# BI5.net
KiCad netlist of a schematic drawn in Altium Designer
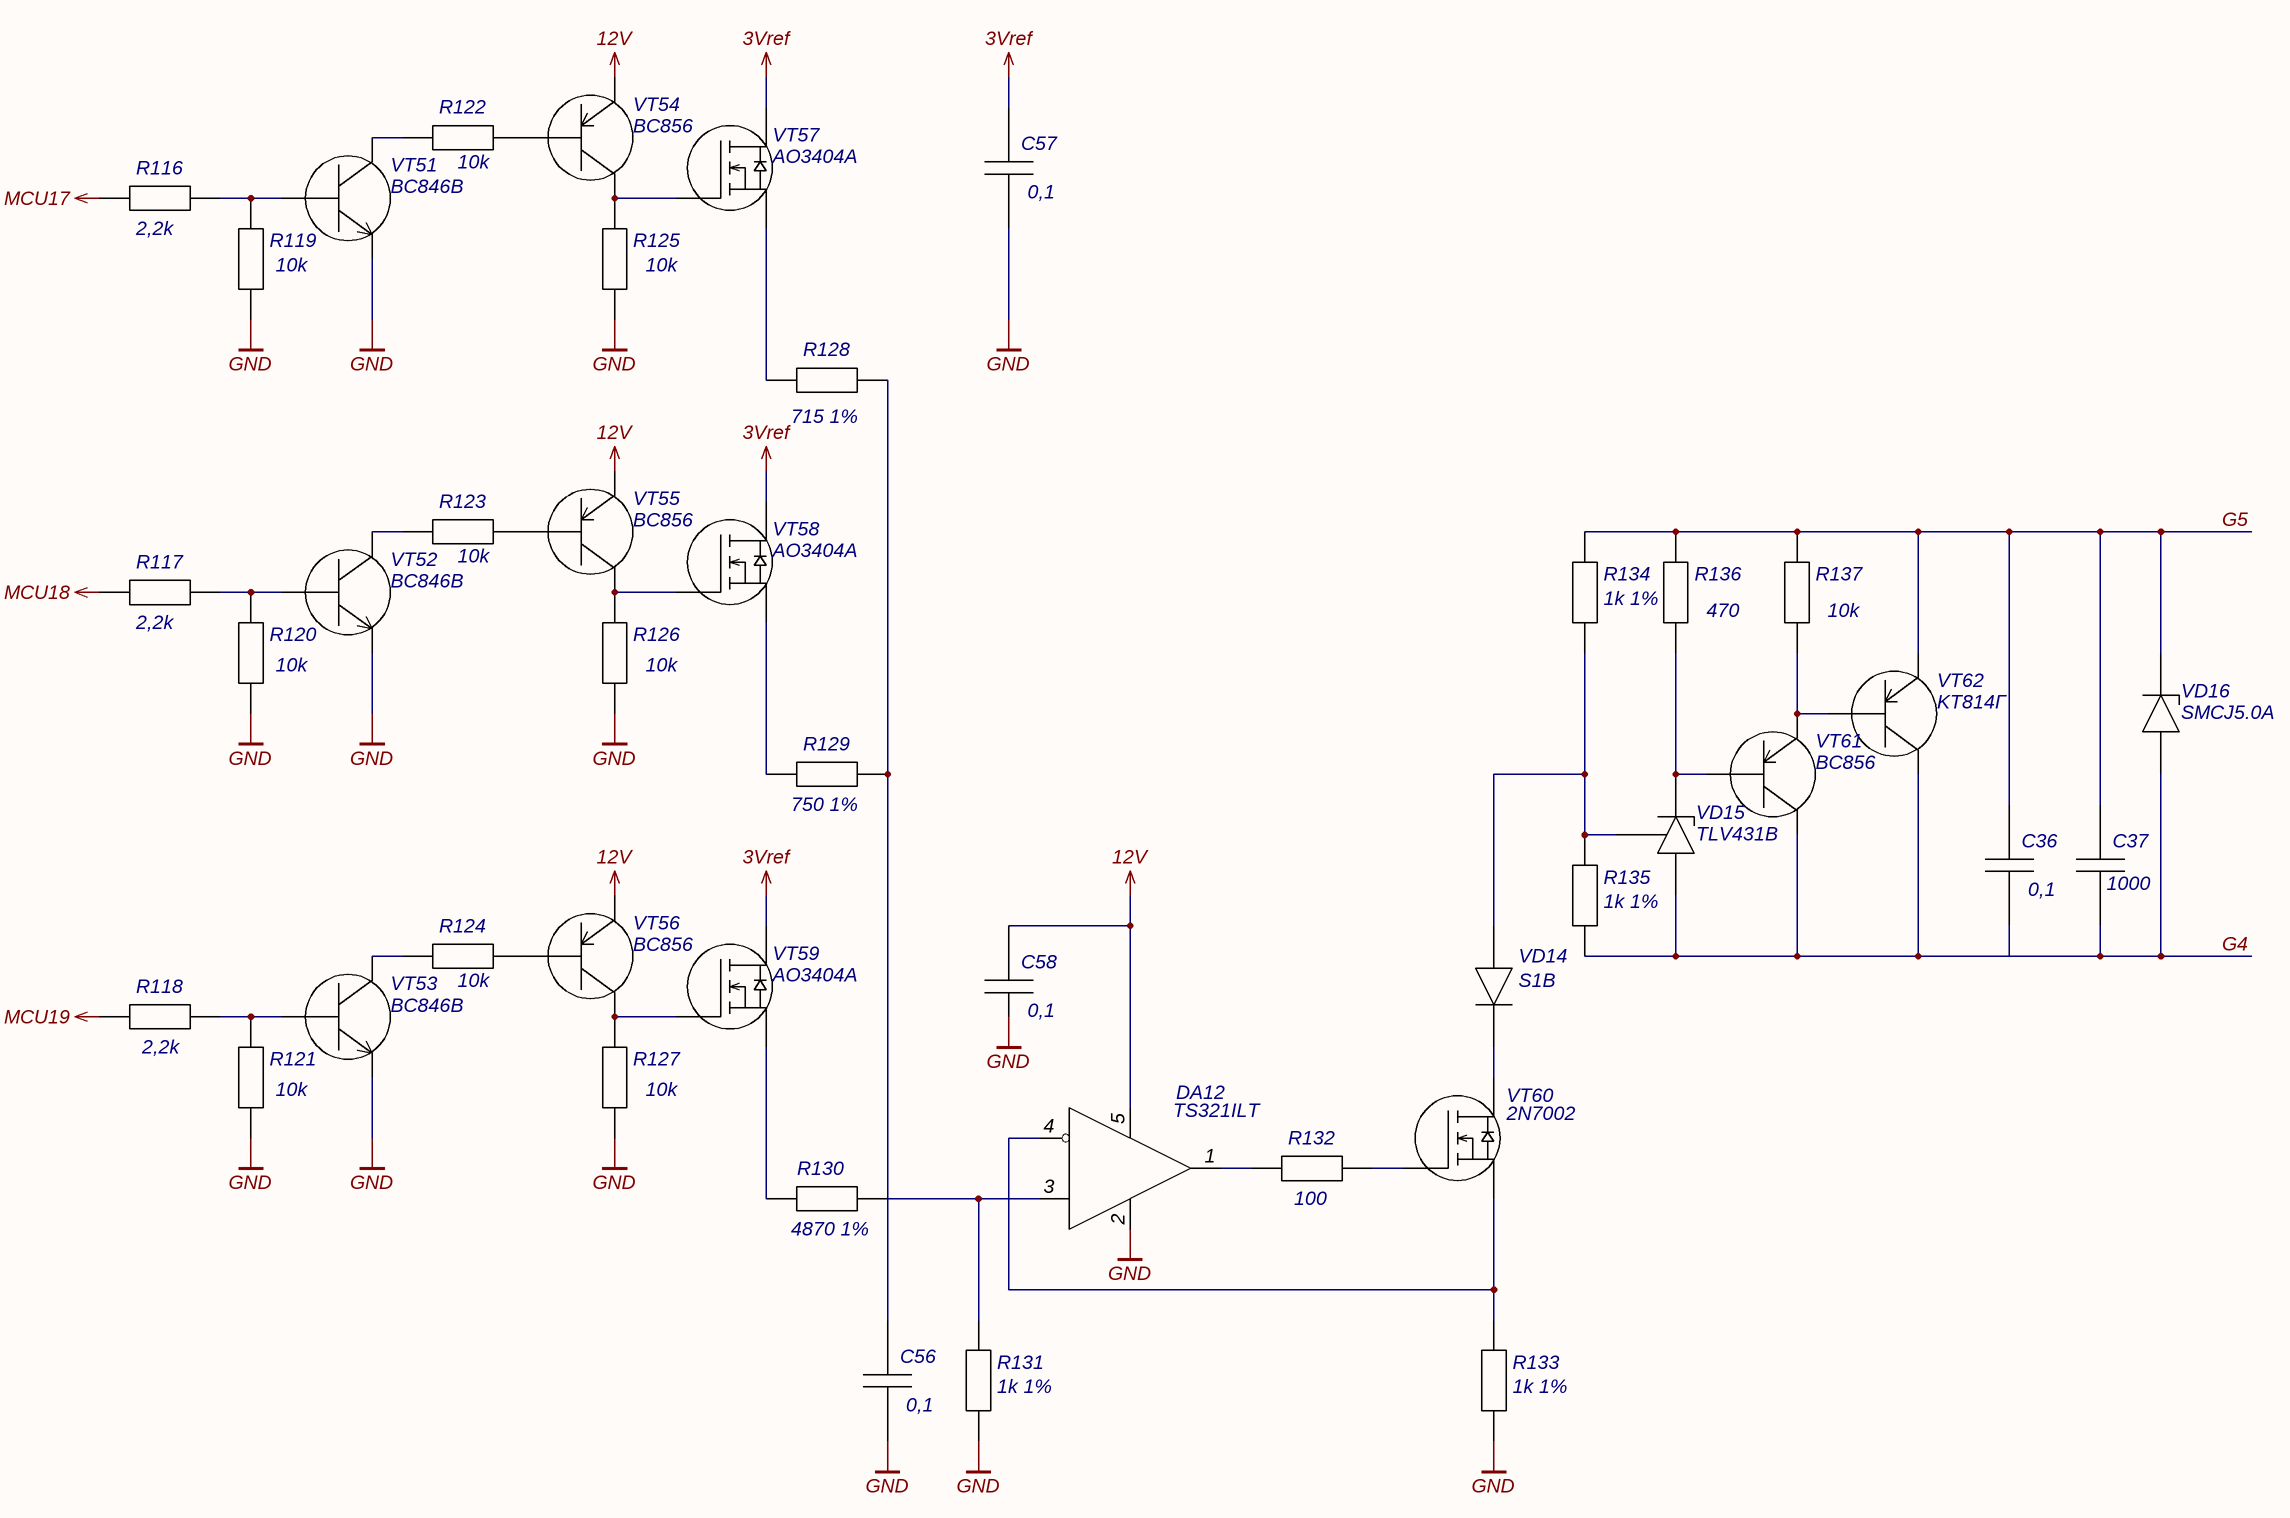
[diagram p0: BI5.SchDoc]

(export (version "E")
  (design (tool "Eeschema 10.0.6"))
  (components
    (comp (ref "C36")
      (value "0,1")
      (footprint "C0603")
      (description "Чип-конденсатор")
      (libsource (lib "Passive") (part "Chip Capasitor"))
    )
    (comp (ref "C37")
      (value "1000")
      (footprint "C0603")
      (description "Чип-конденсатор")
      (libsource (lib "Passive") (part "Chip Capasitor"))
    )
    (comp (ref "C56")
      (value "0,1")
      (footprint "C0603")
      (description "Чип-конденсатор")
      (libsource (lib "Passive") (part "Chip Capasitor"))
    )
    (comp (ref "C57")
      (value "0,1")
      (footprint "C0603")
      (description "Чип-конденсатор")
      (libsource (lib "Passive") (part "Chip Capasitor"))
    )
    (comp (ref "C58")
      (value "0,1")
      (footprint "C0603")
      (description "Чип-конденсатор")
      (libsource (lib "Passive") (part "Chip Capasitor"))
    )
    (comp (ref "DA12")
      (value "TS321ILT")
      (footprint "SOT-23-5")
      (description "1х Операционный усилитель")
      (libsource (lib "Schlib") (part "TS321ILT"))
    )
    (comp (ref "R116")
      (value "2,2k")
      (footprint "R0603")
      (description "Чип-резистор")
      (libsource (lib "Passive") (part "Chip Resistor"))
    )
    (comp (ref "R117")
      (value "2,2k")
      (footprint "R0603")
      (description "Чип-резистор")
      (libsource (lib "Passive") (part "Chip Resistor"))
    )
    (comp (ref "R118")
      (value "2,2k")
      (footprint "R0603")
      (description "Чип-резистор")
      (libsource (lib "Passive") (part "Chip Resistor"))
    )
    (comp (ref "R119")
      (value "10k")
      (footprint "R0603")
      (description "Чип-резистор")
      (libsource (lib "") (part "Chip Resistor_1"))
    )
    (comp (ref "R120")
      (value "10k")
      (footprint "R0603")
      (description "Чип-резистор")
      (libsource (lib "") (part "Chip Resistor_1"))
    )
    (comp (ref "R121")
      (value "10k")
      (footprint "R0603")
      (description "Чип-резистор")
      (libsource (lib "") (part "Chip Resistor_1"))
    )
    (comp (ref "R122")
      (value "10k")
      (footprint "R0603")
      (description "Чип-резистор")
      (libsource (lib "Passive") (part "Chip Resistor"))
    )
    (comp (ref "R123")
      (value "10k")
      (footprint "R0603")
      (description "Чип-резистор")
      (libsource (lib "Passive") (part "Chip Resistor"))
    )
    (comp (ref "R124")
      (value "10k")
      (footprint "R0603")
      (description "Чип-резистор")
      (libsource (lib "Passive") (part "Chip Resistor"))
    )
    (comp (ref "R125")
      (value "10k")
      (footprint "R0603")
      (description "Чип-резистор")
      (libsource (lib "") (part "Chip Resistor_1"))
    )
    (comp (ref "R126")
      (value "10k")
      (footprint "R0603")
      (description "Чип-резистор")
      (libsource (lib "") (part "Chip Resistor_1"))
    )
    (comp (ref "R127")
      (value "10k")
      (footprint "R0603")
      (description "Чип-резистор")
      (libsource (lib "") (part "Chip Resistor_1"))
    )
    (comp (ref "R128")
      (value "715 1%")
      (footprint "R0603")
      (description "Чип-резистор")
      (fields (field (name "PARTNUMBER") "RC0603FR-07715RL"))
      (libsource (lib "Passive") (part "Chip Resistor"))
    )
    (comp (ref "R129")
      (value "750 1%")
      (footprint "R0603")
      (description "Чип-резистор")
      (fields (field (name "PARTNUMBER") "RC0603FR-07750RL"))
      (libsource (lib "Passive") (part "Chip Resistor"))
    )
    (comp (ref "R130")
      (value "4870 1%")
      (footprint "R0603")
      (description "Чип-резистор")
      (fields (field (name "PARTNUMBER") "RC0603FR-074K87L"))
      (libsource (lib "Passive") (part "Chip Resistor"))
    )
    (comp (ref "R131")
      (value "1k 1%")
      (footprint "R0603")
      (description "Чип-резистор")
      (fields (field (name "PARTNUMBER") "CRCW06031K00FKEAC"))
      (libsource (lib "") (part "Chip Resistor_1"))
    )
    (comp (ref "R132")
      (value "100")
      (footprint "R0603")
      (description "Чип-резистор")
      (libsource (lib "Passive") (part "Chip Resistor"))
    )
    (comp (ref "R133")
      (value "1k 1%")
      (footprint "R0603")
      (description "Чип-резистор")
      (fields (field (name "PARTNUMBER") "CRCW06031K00FKEAC"))
      (libsource (lib "") (part "Chip Resistor_1"))
    )
    (comp (ref "R134")
      (value "1k 1%")
      (footprint "R0603")
      (description "Чип-резистор")
      (fields (field (name "PARTNUMBER") "CRCW06031K00FKEAC"))
      (libsource (lib "") (part "Chip Resistor_1"))
    )
    (comp (ref "R135")
      (value "1k 1%")
      (footprint "R0603")
      (description "Чип-резистор")
      (fields (field (name "PARTNUMBER") "CRCW06031K00FKEAC"))
      (libsource (lib "") (part "Chip Resistor_1"))
    )
    (comp (ref "R136")
      (value "470")
      (footprint "R0603")
      (description "Чип-резистор")
      (libsource (lib "") (part "Chip Resistor_1"))
    )
    (comp (ref "R137")
      (value "10k")
      (footprint "R0603")
      (description "Чип-резистор")
      (libsource (lib "") (part "Chip Resistor_1"))
    )
    (comp (ref "VD14")
      (value "S1B")
      (footprint "DO-214AC")
      (description "Диод выпрямительный, 100В")
      (fields (field (name "MANUFACTURER") "Diotec Semiconductor"))
      (libsource (lib "Schlib") (part "S1B"))
    )
    (comp (ref "VD15")
      (value "TLV431B")
      (footprint "SOT-23")
      (description "Стабилитрон регулируемый, 6В")
      (fields (field (name "MANUFACTURER") "Texas Instruments"))
      (libsource (lib "Schlib") (part "TLV431B"))
    )
    (comp (ref "VD16")
      (value "SMCJ5.0A")
      (footprint "DO-214AB")
      (description "Защитный диод, 5В")
      (fields (field (name "MANUFACTURER") "UTD Semiconductor Co.,Ltd"))
      (libsource (lib "Schlib") (part "SMCJ5.0A"))
    )
    (comp (ref "VT51")
      (value "BC846B")
      (footprint "SOT-23")
      (description "Транзистор биполярный NPN, 65В")
      (fields (field (name "MANUFACTURER") "Nexperia B.V."))
      (libsource (lib "Schlib") (part "BC846B"))
    )
    (comp (ref "VT52")
      (value "BC846B")
      (footprint "SOT-23")
      (description "Транзистор биполярный NPN, 65В")
      (fields (field (name "MANUFACTURER") "Nexperia B.V."))
      (libsource (lib "Schlib") (part "BC846B"))
    )
    (comp (ref "VT53")
      (value "BC846B")
      (footprint "SOT-23")
      (description "Транзистор биполярный NPN, 65В")
      (fields (field (name "MANUFACTURER") "Nexperia B.V."))
      (libsource (lib "Schlib") (part "BC846B"))
    )
    (comp (ref "VT54")
      (value "BC856")
      (footprint "SOT-23")
      (description "Транзистор биполярный PNP, 65В")
      (fields (field (name "MANUFACTURER") "Nexperia"))
      (libsource (lib "Schlib") (part "BC856"))
    )
    (comp (ref "VT55")
      (value "BC856")
      (footprint "SOT-23")
      (description "Транзистор биполярный PNP, 65В")
      (fields (field (name "MANUFACTURER") "Nexperia"))
      (libsource (lib "Schlib") (part "BC856"))
    )
    (comp (ref "VT56")
      (value "BC856")
      (footprint "SOT-23")
      (description "Транзистор биполярный PNP, 65В")
      (fields (field (name "MANUFACTURER") "Nexperia"))
      (libsource (lib "Schlib") (part "BC856"))
    )
    (comp (ref "VT57")
      (value "AO3404A")
      (footprint "SOT-23")
      (description "Транзистор MOSFET N-канал, 30В")
      (fields (field (name "MANUFACTURER") "UTD Semiconductor Co.,Ltd"))
      (libsource (lib "Schlib") (part "AO3404A"))
    )
    (comp (ref "VT58")
      (value "AO3404A")
      (footprint "SOT-23")
      (description "Транзистор MOSFET N-канал, 30В")
      (fields (field (name "MANUFACTURER") "UTD Semiconductor Co.,Ltd"))
      (libsource (lib "Schlib") (part "AO3404A"))
    )
    (comp (ref "VT59")
      (value "AO3404A")
      (footprint "SOT-23")
      (description "Транзистор MOSFET N-канал, 30В")
      (fields (field (name "MANUFACTURER") "UTD Semiconductor Co.,Ltd"))
      (libsource (lib "Schlib") (part "AO3404A"))
    )
    (comp (ref "VT60")
      (value "2N7002")
      (footprint "SOT-23")
      (description "Транзистор MOSFET N-канал, 60В")
      (fields (field (name "MANUFACTURER") "UTD Semiconductor Co."))
      (libsource (lib "Schlib") (part "2N7002"))
    )
    (comp (ref "VT61")
      (value "BC856")
      (footprint "SOT-23")
      (description "Транзистор биполярный PNP, 65В")
      (fields (field (name "MANUFACTURER") "Nexperia"))
      (libsource (lib "Schlib") (part "BC856"))
    )
    (comp (ref "VT62")
      (value "KT814Г")
      (footprint "TO-126")
      (description "Транзистор биполярный PNP, 100В")
      (fields (field (name "MANUFACTURER") "АО «ГРУППА КРЕМНИЙ ЭЛ»"))
      (libsource (lib "Schlib") (part "KT814Г"))
    )
  )
  (nets
    (net (code "1") (name "/G4") (class "Default")
      (node (ref "C36") (pin "1") (pinfunction "1_1") (pintype "passive"))
      (node (ref "C37") (pin "1") (pinfunction "1_1") (pintype "passive"))
      (node (ref "R135") (pin "1") (pinfunction "1_1") (pintype "passive"))
      (node (ref "VD15") (pin "1") (pinfunction "1_1") (pintype "passive"))
      (node (ref "VD16") (pin "1") (pinfunction "1_1") (pintype "passive"))
      (node (ref "VT61") (pin "2") (pinfunction "2_2") (pintype "passive"))
      (node (ref "VT62") (pin "2") (pinfunction "2_2") (pintype "passive"))
    )
    (net (code "2") (name "/G5") (class "Default")
      (node (ref "C36") (pin "2") (pinfunction "2_2") (pintype "passive"))
      (node (ref "C37") (pin "2") (pinfunction "2_2") (pintype "passive"))
      (node (ref "R134") (pin "2") (pinfunction "2_2") (pintype "passive"))
      (node (ref "R136") (pin "2") (pinfunction "2_2") (pintype "passive"))
      (node (ref "R137") (pin "2") (pinfunction "2_2") (pintype "passive"))
      (node (ref "VD16") (pin "2") (pinfunction "2_2") (pintype "passive"))
      (node (ref "VT62") (pin "1") (pinfunction "1_1") (pintype "passive"))
    )
    (net (code "3") (name "3Vref") (class "Default")
      (node (ref "C57") (pin "2") (pinfunction "2_2") (pintype "passive"))
      (node (ref "VT57") (pin "2") (pinfunction "D_2") (pintype "passive"))
      (node (ref "VT58") (pin "2") (pinfunction "D_2") (pintype "passive"))
      (node (ref "VT59") (pin "2") (pinfunction "D_2") (pintype "passive"))
    )
    (net (code "4") (name "12V") (class "Default")
      (node (ref "C58") (pin "2") (pinfunction "2_2") (pintype "passive"))
      (node (ref "DA12") (pin "5") (pinfunction "Vcc_5") (pintype "passive"))
      (node (ref "VT54") (pin "1") (pinfunction "1_1") (pintype "passive"))
      (node (ref "VT55") (pin "1") (pinfunction "1_1") (pintype "passive"))
      (node (ref "VT56") (pin "1") (pinfunction "1_1") (pintype "passive"))
    )
    (net (code "5") (name "GND") (class "Default")
      (node (ref "C56") (pin "1") (pinfunction "1_1") (pintype "passive"))
      (node (ref "C57") (pin "1") (pinfunction "1_1") (pintype "passive"))
      (node (ref "DA12") (pin "2") (pinfunction "GND_2") (pintype "passive"))
      (node (ref "R119") (pin "1") (pinfunction "1_1") (pintype "passive"))
      (node (ref "R120") (pin "1") (pinfunction "1_1") (pintype "passive"))
      (node (ref "R121") (pin "1") (pinfunction "1_1") (pintype "passive"))
      (node (ref "R125") (pin "1") (pinfunction "1_1") (pintype "passive"))
      (node (ref "R126") (pin "1") (pinfunction "1_1") (pintype "passive"))
      (node (ref "R127") (pin "1") (pinfunction "1_1") (pintype "passive"))
      (node (ref "R131") (pin "1") (pinfunction "1_1") (pintype "passive"))
      (node (ref "R133") (pin "1") (pinfunction "1_1") (pintype "passive"))
      (node (ref "VT51") (pin "2") (pinfunction "E_2") (pintype "passive"))
      (node (ref "VT52") (pin "2") (pinfunction "E_2") (pintype "passive"))
      (node (ref "VT53") (pin "2") (pinfunction "E_2") (pintype "passive"))
    )
    (net (code "6") (name "MCU17") (class "Default")
      (node (ref "R116") (pin "1") (pinfunction "1_1") (pintype "passive"))
    )
    (net (code "7") (name "MCU18") (class "Default")
      (node (ref "R117") (pin "1") (pinfunction "1_1") (pintype "passive"))
    )
    (net (code "8") (name "MCU19") (class "Default")
      (node (ref "R118") (pin "1") (pinfunction "1_1") (pintype "passive"))
    )
    (net (code "9") (name "Net-(DA12-+)") (class "Default")
      (node (ref "C56") (pin "2") (pinfunction "2_2") (pintype "passive"))
      (node (ref "DA12") (pin "3") (pinfunction "+_3") (pintype "passive"))
      (node (ref "R128") (pin "2") (pinfunction "2_2") (pintype "passive"))
      (node (ref "R129") (pin "2") (pinfunction "2_2") (pintype "passive"))
      (node (ref "R130") (pin "2") (pinfunction "2_2") (pintype "passive"))
      (node (ref "R131") (pin "2") (pinfunction "2_2") (pintype "passive"))
    )
    (net (code "10") (name "Net-(DA12--)") (class "Default")
      (node (ref "DA12") (pin "4") (pinfunction "-_4") (pintype "passive"))
      (node (ref "R133") (pin "2") (pinfunction "2_2") (pintype "passive"))
      (node (ref "VT60") (pin "3") (pinfunction "S_3") (pintype "passive"))
    )
    (net (code "11") (name "Net-(DA12-OUT)") (class "Default")
      (node (ref "DA12") (pin "1") (pinfunction "OUT_1") (pintype "passive"))
      (node (ref "R132") (pin "1") (pinfunction "1_1") (pintype "passive"))
    )
    (net (code "12") (name "Net-(R122-Pad2)") (class "Default")
      (node (ref "R122") (pin "2") (pinfunction "2_2") (pintype "passive"))
      (node (ref "VT54") (pin "3") (pinfunction "3_3") (pintype "passive"))
    )
    (net (code "13") (name "Net-(R123-Pad2)") (class "Default")
      (node (ref "R123") (pin "2") (pinfunction "2_2") (pintype "passive"))
      (node (ref "VT55") (pin "3") (pinfunction "3_3") (pintype "passive"))
    )
    (net (code "14") (name "Net-(R124-Pad2)") (class "Default")
      (node (ref "R124") (pin "2") (pinfunction "2_2") (pintype "passive"))
      (node (ref "VT56") (pin "3") (pinfunction "3_3") (pintype "passive"))
    )
    (net (code "15") (name "Net-(R134-Pad1)") (class "Default")
      (node (ref "R134") (pin "1") (pinfunction "1_1") (pintype "passive"))
      (node (ref "R135") (pin "2") (pinfunction "2_2") (pintype "passive"))
      (node (ref "VD14") (pin "1") (pinfunction "1_1") (pintype "passive"))
      (node (ref "VD15") (pin "3") (pinfunction "3_3") (pintype "passive"))
    )
    (net (code "16") (name "Net-(R136-Pad1)") (class "Default")
      (node (ref "R136") (pin "1") (pinfunction "1_1") (pintype "passive"))
      (node (ref "VD15") (pin "2") (pinfunction "2_2") (pintype "passive"))
      (node (ref "VT61") (pin "3") (pinfunction "3_3") (pintype "passive"))
    )
    (net (code "17") (name "Net-(R137-Pad1)") (class "Default")
      (node (ref "R137") (pin "1") (pinfunction "1_1") (pintype "passive"))
      (node (ref "VT61") (pin "1") (pinfunction "1_1") (pintype "passive"))
      (node (ref "VT62") (pin "3") (pinfunction "3_3") (pintype "passive"))
    )
    (net (code "18") (name "Net-(VT51-B)") (class "Default")
      (node (ref "R116") (pin "2") (pinfunction "2_2") (pintype "passive"))
      (node (ref "R119") (pin "2") (pinfunction "2_2") (pintype "passive"))
      (node (ref "VT51") (pin "1") (pinfunction "B_1") (pintype "passive"))
    )
    (net (code "19") (name "Net-(VT51-C)") (class "Default")
      (node (ref "R122") (pin "1") (pinfunction "1_1") (pintype "passive"))
      (node (ref "VT51") (pin "3") (pinfunction "C_3") (pintype "passive"))
    )
    (net (code "20") (name "Net-(VT52-B)") (class "Default")
      (node (ref "R117") (pin "2") (pinfunction "2_2") (pintype "passive"))
      (node (ref "R120") (pin "2") (pinfunction "2_2") (pintype "passive"))
      (node (ref "VT52") (pin "1") (pinfunction "B_1") (pintype "passive"))
    )
    (net (code "21") (name "Net-(VT52-C)") (class "Default")
      (node (ref "R123") (pin "1") (pinfunction "1_1") (pintype "passive"))
      (node (ref "VT52") (pin "3") (pinfunction "C_3") (pintype "passive"))
    )
    (net (code "22") (name "Net-(VT53-B)") (class "Default")
      (node (ref "R118") (pin "2") (pinfunction "2_2") (pintype "passive"))
      (node (ref "R121") (pin "2") (pinfunction "2_2") (pintype "passive"))
      (node (ref "VT53") (pin "1") (pinfunction "B_1") (pintype "passive"))
    )
    (net (code "23") (name "Net-(VT53-C)") (class "Default")
      (node (ref "R124") (pin "1") (pinfunction "1_1") (pintype "passive"))
      (node (ref "VT53") (pin "3") (pinfunction "C_3") (pintype "passive"))
    )
    (net (code "24") (name "Net-(VT57-G)") (class "Default")
      (node (ref "R125") (pin "2") (pinfunction "2_2") (pintype "passive"))
      (node (ref "VT54") (pin "2") (pinfunction "2_2") (pintype "passive"))
      (node (ref "VT57") (pin "1") (pinfunction "G_1") (pintype "passive"))
    )
    (net (code "25") (name "Net-(VT57-S)") (class "Default")
      (node (ref "R128") (pin "1") (pinfunction "1_1") (pintype "passive"))
      (node (ref "VT57") (pin "3") (pinfunction "S_3") (pintype "passive"))
    )
    (net (code "26") (name "Net-(VT58-G)") (class "Default")
      (node (ref "R126") (pin "2") (pinfunction "2_2") (pintype "passive"))
      (node (ref "VT55") (pin "2") (pinfunction "2_2") (pintype "passive"))
      (node (ref "VT58") (pin "1") (pinfunction "G_1") (pintype "passive"))
    )
    (net (code "27") (name "Net-(VT58-S)") (class "Default")
      (node (ref "R129") (pin "1") (pinfunction "1_1") (pintype "passive"))
      (node (ref "VT58") (pin "3") (pinfunction "S_3") (pintype "passive"))
    )
    (net (code "28") (name "Net-(VT59-G)") (class "Default")
      (node (ref "R127") (pin "2") (pinfunction "2_2") (pintype "passive"))
      (node (ref "VT56") (pin "2") (pinfunction "2_2") (pintype "passive"))
      (node (ref "VT59") (pin "1") (pinfunction "G_1") (pintype "passive"))
    )
    (net (code "29") (name "Net-(VT59-S)") (class "Default")
      (node (ref "R130") (pin "1") (pinfunction "1_1") (pintype "passive"))
      (node (ref "VT59") (pin "3") (pinfunction "S_3") (pintype "passive"))
    )
    (net (code "30") (name "Net-(VT60-D)") (class "Default")
      (node (ref "VD14") (pin "2") (pinfunction "2_2") (pintype "passive"))
      (node (ref "VT60") (pin "2") (pinfunction "D_2") (pintype "passive"))
    )
    (net (code "31") (name "Net-(VT60-G)") (class "Default")
      (node (ref "R132") (pin "2") (pinfunction "2_2") (pintype "passive"))
      (node (ref "VT60") (pin "1") (pinfunction "G_1") (pintype "passive"))
    )
    (net (code "32") (name "unconnected-(C58-Pad1)") (class "Default")
      (node (ref "C58") (pin "1") (pinfunction "1_1") (pintype "passive"))
    )
  )
)
